# g_plus_shield_v1.net
KiCad netlist of a schematic drawn in EAGLE
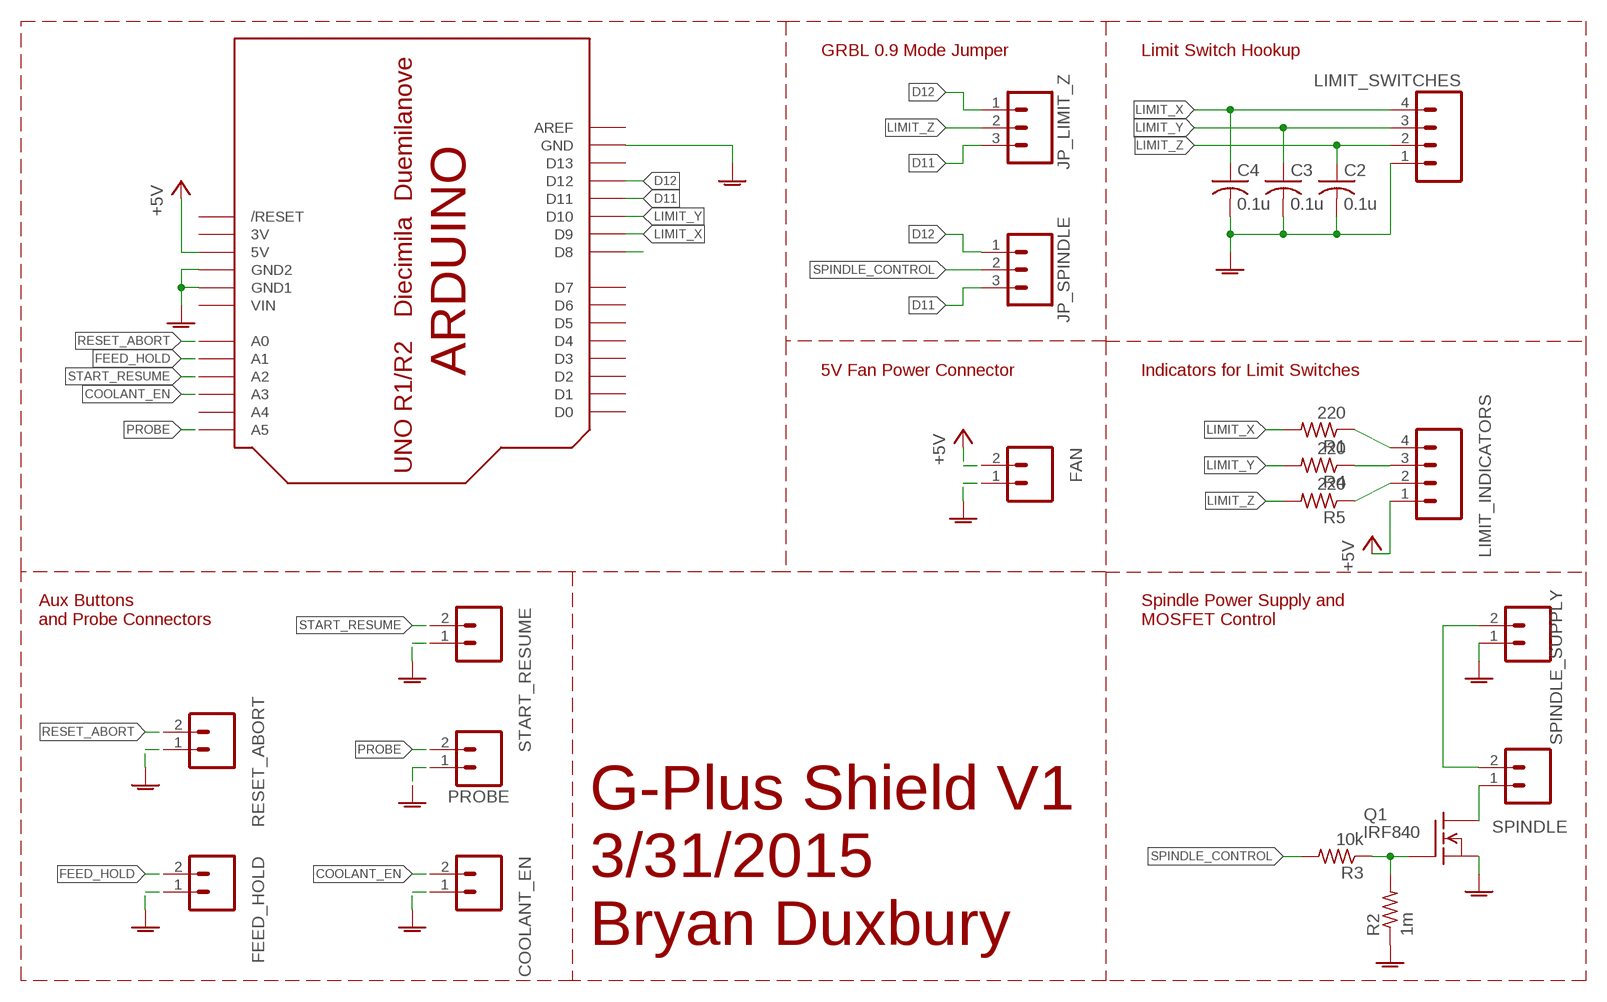
[diagram p0: schematic, sheet 1]

(export (version "E")
  (design (tool "Eeschema 10.0.6"))
  (components
    (comp (ref "C2")
      (value "0.1u")
      (footprint "eagle-import:C0805K")
      (libsource (lib "eagle-import") (part "C-USC0805K"))
    )
    (comp (ref "C3")
      (value "0.1u")
      (footprint "eagle-import:C0805K")
      (libsource (lib "eagle-import") (part "C-USC0805K"))
    )
    (comp (ref "C4")
      (value "0.1u")
      (footprint "eagle-import:C0805K")
      (libsource (lib "eagle-import") (part "C-USC0805K"))
    )
    (comp (ref "COOLANT_EN")
      (value "M02POLAR")
      (footprint "eagle-import:MOLEX-1X2")
      (libsource (lib "eagle-import") (part "M02POLAR"))
    )
    (comp (ref "FAN")
      (value "M02POLAR")
      (footprint "eagle-import:MOLEX-1X2")
      (libsource (lib "eagle-import") (part "M02POLAR"))
    )
    (comp (ref "FEED_HOLD")
      (value "M02POLAR")
      (footprint "eagle-import:MOLEX-1X2")
      (libsource (lib "eagle-import") (part "M02POLAR"))
    )
    (comp (ref "JP_LIMIT_Z")
      (value "M03POLAR")
      (footprint "eagle-import:MOLEX-1X3")
      (libsource (lib "eagle-import") (part "M03POLAR"))
    )
    (comp (ref "JP_SPINDLE")
      (value "M03POLAR")
      (footprint "eagle-import:MOLEX-1X3")
      (libsource (lib "eagle-import") (part "M03POLAR"))
    )
    (comp (ref "LIMIT_INDICATORS")
      (value "M04POLAR")
      (footprint "eagle-import:MOLEX-1X4")
      (libsource (lib "eagle-import") (part "M04POLAR"))
    )
    (comp (ref "LIMIT_SWITCHES")
      (value "M04POLAR")
      (footprint "eagle-import:MOLEX-1X4")
      (libsource (lib "eagle-import") (part "M04POLAR"))
    )
    (comp (ref "PROBE")
      (value "M02POLAR")
      (footprint "eagle-import:MOLEX-1X2")
      (libsource (lib "eagle-import") (part "M02POLAR"))
    )
    (comp (ref "Q1")
      (value "IRF840")
      (footprint "eagle-import:TO220")
      (libsource (lib "eagle-import") (part "IRF840"))
    )
    (comp (ref "R1")
      (value "220")
      (footprint "eagle-import:M0805")
      (libsource (lib "eagle-import") (part "R-US_M0805"))
    )
    (comp (ref "R2")
      (value "1m")
      (footprint "eagle-import:M0805")
      (libsource (lib "eagle-import") (part "R-US_M0805"))
    )
    (comp (ref "R3")
      (value "10k")
      (footprint "eagle-import:M0805")
      (libsource (lib "eagle-import") (part "R-US_M0805"))
    )
    (comp (ref "R4")
      (value "220")
      (footprint "eagle-import:M0805")
      (libsource (lib "eagle-import") (part "R-US_M0805"))
    )
    (comp (ref "R5")
      (value "220")
      (footprint "eagle-import:M0805")
      (libsource (lib "eagle-import") (part "R-US_M0805"))
    )
    (comp (ref "RESET_ABORT")
      (value "M02POLAR")
      (footprint "eagle-import:MOLEX-1X2")
      (libsource (lib "eagle-import") (part "M02POLAR"))
    )
    (comp (ref "SPINDLE")
      (value "M02POLAR")
      (footprint "eagle-import:MOLEX-1X2")
      (libsource (lib "eagle-import") (part "M02POLAR"))
    )
    (comp (ref "SPINDLE_SUPPLY")
      (value "M02POLAR")
      (footprint "eagle-import:MOLEX-1X2")
      (libsource (lib "eagle-import") (part "M02POLAR"))
    )
    (comp (ref "START_RESUME")
      (value "M02POLAR")
      (footprint "eagle-import:MOLEX-1X2")
      (libsource (lib "eagle-import") (part "M02POLAR"))
    )
    (comp (ref "U$1")
      (value "ARDUINO-NODIM")
      (footprint "eagle-import:ARDUINO-NODIM")
      (libsource (lib "eagle-import") (part "ARDUINO-NODIM"))
    )
  )
  (nets
    (net (code "1") (name "+5V") (class "Default")
      (node (ref "FAN") (pin "2") (pinfunction "2_2") (pintype "passive"))
      (node (ref "LIMIT_INDICATORS") (pin "1") (pinfunction "1_1") (pintype "passive"))
      (node (ref "U$1") (pin "5V") (pinfunction "5V_5V") (pintype "power_in"))
    )
    (net (code "2") (name "/3V") (class "Default")
      (node (ref "U$1") (pin "3V") (pinfunction "3V_3V") (pintype "power_in"))
    )
    (net (code "3") (name "/VIN") (class "Default")
      (node (ref "U$1") (pin "VIN") (pinfunction "VIN_VIN") (pintype "power_in"))
    )
    (net (code "4") (name "COOLANT_EN") (class "Default")
      (node (ref "COOLANT_EN") (pin "2") (pinfunction "2_2") (pintype "passive"))
      (node (ref "U$1") (pin "A3") (pinfunction "A3_A3") (pintype "bidirectional"))
    )
    (net (code "5") (name "D11") (class "Default")
      (node (ref "JP_LIMIT_Z") (pin "3") (pinfunction "3_3") (pintype "passive"))
      (node (ref "JP_SPINDLE") (pin "3") (pinfunction "3_3") (pintype "passive"))
      (node (ref "U$1") (pin "D11") (pinfunction "D11_D11") (pintype "bidirectional"))
    )
    (net (code "6") (name "D12") (class "Default")
      (node (ref "JP_LIMIT_Z") (pin "1") (pinfunction "1_1") (pintype "passive"))
      (node (ref "JP_SPINDLE") (pin "1") (pinfunction "1_1") (pintype "passive"))
      (node (ref "U$1") (pin "D12") (pinfunction "D12_D12") (pintype "bidirectional"))
    )
    (net (code "7") (name "FEED_HOLD") (class "Default")
      (node (ref "FEED_HOLD") (pin "2") (pinfunction "2_2") (pintype "passive"))
      (node (ref "U$1") (pin "A1") (pinfunction "A1_A1") (pintype "bidirectional"))
    )
    (net (code "8") (name "GNDA") (class "Default")
      (node (ref "C2") (pin "2") (pinfunction "2_2") (pintype "passive"))
      (node (ref "C3") (pin "2") (pinfunction "2_2") (pintype "passive"))
      (node (ref "C4") (pin "2") (pinfunction "2_2") (pintype "passive"))
      (node (ref "COOLANT_EN") (pin "1") (pinfunction "1_1") (pintype "passive"))
      (node (ref "FAN") (pin "1") (pinfunction "1_1") (pintype "passive"))
      (node (ref "FEED_HOLD") (pin "1") (pinfunction "1_1") (pintype "passive"))
      (node (ref "LIMIT_SWITCHES") (pin "1") (pinfunction "1_1") (pintype "passive"))
      (node (ref "PROBE") (pin "1") (pinfunction "1_1") (pintype "passive"))
      (node (ref "Q1") (pin "3") (pinfunction "S_3") (pintype "passive"))
      (node (ref "R2") (pin "1") (pinfunction "1_1") (pintype "passive"))
      (node (ref "RESET_ABORT") (pin "1") (pinfunction "1_1") (pintype "passive"))
      (node (ref "SPINDLE_SUPPLY") (pin "1") (pinfunction "1_1") (pintype "passive"))
      (node (ref "START_RESUME") (pin "1") (pinfunction "1_1") (pintype "passive"))
      (node (ref "U$1") (pin "GND") (pinfunction "GND_GND") (pintype "power_in"))
      (node (ref "U$1") (pin "GND1") (pinfunction "GND1_GND1") (pintype "power_in"))
      (node (ref "U$1") (pin "GND2") (pinfunction "GND2_GND2") (pintype "power_in"))
    )
    (net (code "9") (name "LIMIT_X") (class "Default")
      (node (ref "C4") (pin "1") (pinfunction "1_1") (pintype "passive"))
      (node (ref "LIMIT_SWITCHES") (pin "4") (pinfunction "4_4") (pintype "passive"))
      (node (ref "R1") (pin "2") (pinfunction "2_2") (pintype "passive"))
      (node (ref "U$1") (pin "D9") (pinfunction "D9_D9") (pintype "bidirectional"))
    )
    (net (code "10") (name "LIMIT_Y") (class "Default")
      (node (ref "C3") (pin "1") (pinfunction "1_1") (pintype "passive"))
      (node (ref "LIMIT_SWITCHES") (pin "3") (pinfunction "3_3") (pintype "passive"))
      (node (ref "R4") (pin "2") (pinfunction "2_2") (pintype "passive"))
      (node (ref "U$1") (pin "D10") (pinfunction "D10_D10") (pintype "bidirectional"))
    )
    (net (code "11") (name "LIMIT_Z") (class "Default")
      (node (ref "C2") (pin "1") (pinfunction "1_1") (pintype "passive"))
      (node (ref "JP_LIMIT_Z") (pin "2") (pinfunction "2_2") (pintype "passive"))
      (node (ref "LIMIT_SWITCHES") (pin "2") (pinfunction "2_2") (pintype "passive"))
      (node (ref "R5") (pin "2") (pinfunction "2_2") (pintype "passive"))
    )
    (net (code "12") (name "Net-(LIMIT_INDICATORS-Pad2)") (class "Default")
      (node (ref "LIMIT_INDICATORS") (pin "2") (pinfunction "2_2") (pintype "passive"))
      (node (ref "R5") (pin "1") (pinfunction "1_1") (pintype "passive"))
    )
    (net (code "13") (name "Net-(LIMIT_INDICATORS-Pad3)") (class "Default")
      (node (ref "LIMIT_INDICATORS") (pin "3") (pinfunction "3_3") (pintype "passive"))
      (node (ref "R4") (pin "1") (pinfunction "1_1") (pintype "passive"))
    )
    (net (code "14") (name "Net-(LIMIT_INDICATORS-Pad4)") (class "Default")
      (node (ref "LIMIT_INDICATORS") (pin "4") (pinfunction "4_4") (pintype "passive"))
      (node (ref "R1") (pin "1") (pinfunction "1_1") (pintype "passive"))
    )
    (net (code "15") (name "Net-(Q1-D)") (class "Default")
      (node (ref "Q1") (pin "2") (pinfunction "D_2") (pintype "passive"))
      (node (ref "SPINDLE") (pin "1") (pinfunction "1_1") (pintype "passive"))
    )
    (net (code "16") (name "Net-(Q1-G)") (class "Default")
      (node (ref "Q1") (pin "1") (pinfunction "G_1") (pintype "passive"))
      (node (ref "R2") (pin "2") (pinfunction "2_2") (pintype "passive"))
      (node (ref "R3") (pin "1") (pinfunction "1_1") (pintype "passive"))
    )
    (net (code "17") (name "Net-(SPINDLE-Pad2)") (class "Default")
      (node (ref "SPINDLE") (pin "2") (pinfunction "2_2") (pintype "passive"))
      (node (ref "SPINDLE_SUPPLY") (pin "2") (pinfunction "2_2") (pintype "passive"))
    )
    (net (code "18") (name "PROBE") (class "Default")
      (node (ref "PROBE") (pin "2") (pinfunction "2_2") (pintype "passive"))
      (node (ref "U$1") (pin "A5") (pinfunction "A5_A5") (pintype "bidirectional"))
    )
    (net (code "19") (name "RESET_ABORT") (class "Default")
      (node (ref "RESET_ABORT") (pin "2") (pinfunction "2_2") (pintype "passive"))
      (node (ref "U$1") (pin "A0") (pinfunction "A0_A0") (pintype "bidirectional"))
    )
    (net (code "20") (name "SPINDLE_CONTROL") (class "Default")
      (node (ref "JP_SPINDLE") (pin "2") (pinfunction "2_2") (pintype "passive"))
      (node (ref "R3") (pin "2") (pinfunction "2_2") (pintype "passive"))
    )
    (net (code "21") (name "START_RESUME") (class "Default")
      (node (ref "START_RESUME") (pin "2") (pinfunction "2_2") (pintype "passive"))
      (node (ref "U$1") (pin "A2") (pinfunction "A2_A2") (pintype "bidirectional"))
    )
    (net (code "22") (name "unconnected-(U$1-PadA4)") (class "Default")
      (node (ref "U$1") (pin "A4") (pinfunction "A4_A4") (pintype "bidirectional"))
    )
    (net (code "23") (name "unconnected-(U$1-PadAREF)") (class "Default")
      (node (ref "U$1") (pin "AREF") (pinfunction "AREF_AREF") (pintype "bidirectional"))
    )
    (net (code "24") (name "unconnected-(U$1-PadD0)") (class "Default")
      (node (ref "U$1") (pin "D0") (pinfunction "D0_D0") (pintype "bidirectional"))
    )
    (net (code "25") (name "unconnected-(U$1-PadD1)") (class "Default")
      (node (ref "U$1") (pin "D1") (pinfunction "D1_D1") (pintype "bidirectional"))
    )
    (net (code "26") (name "unconnected-(U$1-PadD2)") (class "Default")
      (node (ref "U$1") (pin "D2") (pinfunction "D2_D2") (pintype "bidirectional"))
    )
    (net (code "27") (name "unconnected-(U$1-PadD3)") (class "Default")
      (node (ref "U$1") (pin "D3") (pinfunction "D3_D3") (pintype "bidirectional"))
    )
    (net (code "28") (name "unconnected-(U$1-PadD4)") (class "Default")
      (node (ref "U$1") (pin "D4") (pinfunction "D4_D4") (pintype "bidirectional"))
    )
    (net (code "29") (name "unconnected-(U$1-PadD5)") (class "Default")
      (node (ref "U$1") (pin "D5") (pinfunction "D5_D5") (pintype "bidirectional"))
    )
    (net (code "30") (name "unconnected-(U$1-PadD6)") (class "Default")
      (node (ref "U$1") (pin "D6") (pinfunction "D6_D6") (pintype "bidirectional"))
    )
    (net (code "31") (name "unconnected-(U$1-PadD7)") (class "Default")
      (node (ref "U$1") (pin "D7") (pinfunction "D7_D7") (pintype "bidirectional"))
    )
    (net (code "32") (name "unconnected-(U$1-PadD8)") (class "Default")
      (node (ref "U$1") (pin "D8") (pinfunction "D8_D8") (pintype "bidirectional"))
    )
    (net (code "33") (name "unconnected-(U$1-PadD13)") (class "Default")
      (node (ref "U$1") (pin "D13") (pinfunction "D13_D13") (pintype "bidirectional"))
    )
    (net (code "34") (name "unconnected-(U$1-{slash}RESET-PadRESET)") (class "Default")
      (node (ref "U$1") (pin "RESET") (pinfunction "/RESET_RESET") (pintype "bidirectional"))
    )
  )
)
